# Project_2.net
KiCad netlist of a schematic drawn in EAGLE
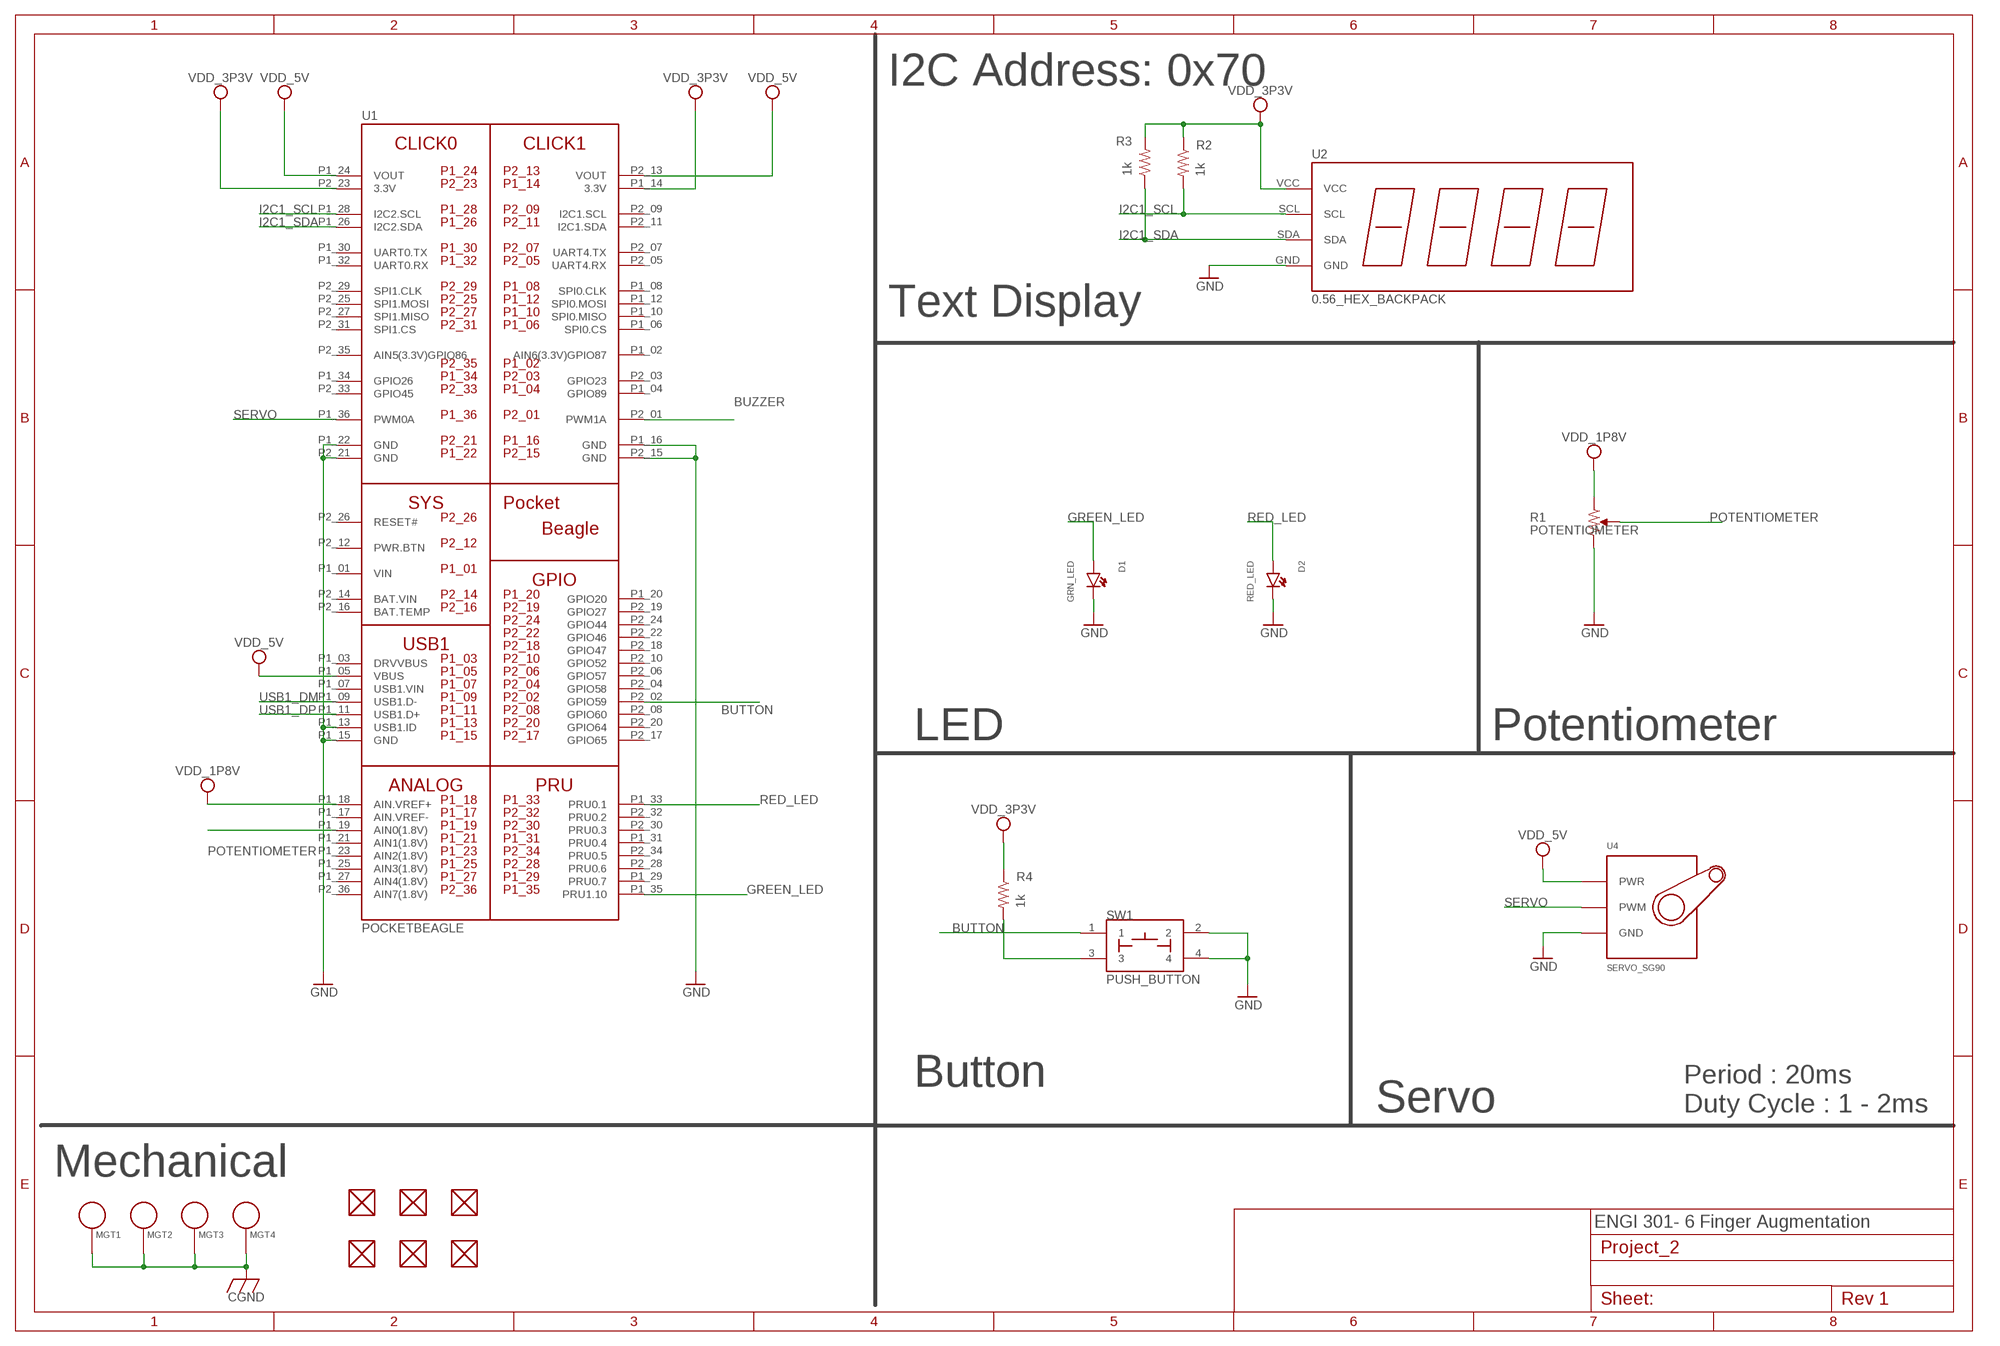
[diagram p0: schematic, sheet 1]

(export (version "E")
  (design (tool "Eeschema 10.0.6"))
  (components
    (comp (ref "D1")
      (value "GRN_LED")
      (footprint "eagle-import:EIA-STD")
      (libsource (lib "eagle-import") (part "LED"))
    )
    (comp (ref "D2")
      (value "RED_LED")
      (footprint "eagle-import:EIA-STD")
      (libsource (lib "eagle-import") (part "LED"))
    )
    (comp (ref "FUD1")
      (value "FIDUCIAL")
      (footprint "eagle-import:FIDUCIAL_40MIL")
      (libsource (lib "eagle-import") (part "FIDUCIAL"))
    )
    (comp (ref "FUD2")
      (value "FIDUCIAL")
      (footprint "eagle-import:FIDUCIAL_40MIL")
      (libsource (lib "eagle-import") (part "FIDUCIAL"))
    )
    (comp (ref "FUD3")
      (value "FIDUCIAL")
      (footprint "eagle-import:FIDUCIAL_40MIL")
      (libsource (lib "eagle-import") (part "FIDUCIAL"))
    )
    (comp (ref "FUD4")
      (value "FIDUCIAL")
      (footprint "eagle-import:FIDUCIAL_40MIL")
      (libsource (lib "eagle-import") (part "FIDUCIAL"))
    )
    (comp (ref "FUD5")
      (value "FIDUCIAL")
      (footprint "eagle-import:FIDUCIAL_40MIL")
      (libsource (lib "eagle-import") (part "FIDUCIAL"))
    )
    (comp (ref "FUD6")
      (value "FIDUCIAL")
      (footprint "eagle-import:FIDUCIAL_40MIL")
      (libsource (lib "eagle-import") (part "FIDUCIAL"))
    )
    (comp (ref "MGT1")
      (value "MOUNTING_HOLE")
      (footprint "eagle-import:MOUNTING_HOLE")
      (libsource (lib "eagle-import") (part "MOUNTING_HOLE"))
    )
    (comp (ref "MGT2")
      (value "MOUNTING_HOLE")
      (footprint "eagle-import:MOUNTING_HOLE")
      (libsource (lib "eagle-import") (part "MOUNTING_HOLE"))
    )
    (comp (ref "MGT3")
      (value "MOUNTING_HOLE")
      (footprint "eagle-import:MOUNTING_HOLE")
      (libsource (lib "eagle-import") (part "MOUNTING_HOLE"))
    )
    (comp (ref "MGT4")
      (value "MOUNTING_HOLE")
      (footprint "eagle-import:MOUNTING_HOLE")
      (libsource (lib "eagle-import") (part "MOUNTING_HOLE"))
    )
    (comp (ref "R1")
      (value "POTENTIOMETER")
      (footprint "eagle-import:POT-PO90S")
      (libsource (lib "eagle-import") (part "POTENTIOMETER"))
    )
    (comp (ref "R2")
      (value "1k")
      (footprint "eagle-import:R0603")
      (libsource (lib "eagle-import") (part "R_R0603"))
    )
    (comp (ref "R3")
      (value "1k")
      (footprint "eagle-import:R0603")
      (libsource (lib "eagle-import") (part "R_R0603"))
    )
    (comp (ref "R4")
      (value "1k")
      (footprint "eagle-import:R0603")
      (libsource (lib "eagle-import") (part "R_R0603"))
    )
    (comp (ref "SW1")
      (value "PUSH_BUTTON")
      (footprint "eagle-import:BUTTON_12.5MM")
      (libsource (lib "eagle-import") (part "PUSH_BUTTON"))
    )
    (comp (ref "U1")
      (value "POCKETBEAGLE")
      (footprint "eagle-import:POCKETBEAGLE")
      (libsource (lib "eagle-import") (part "POCKETBEAGLE"))
    )
    (comp (ref "U2")
      (value "0.56_HEX_BACKPACK")
      (footprint "eagle-import:0.56_HEX_BACKPACK")
      (libsource (lib "eagle-import") (part "0.56_HEX_BACKPACK"))
    )
    (comp (ref "U4")
      (value "SERVO_SG90")
      (footprint "eagle-import:SERVO-X1")
      (libsource (lib "eagle-import") (part "SERVO_SG90"))
    )
  )
  (nets
    (net (code "1") (name "/BAT.VIN") (class "Default")
      (node (ref "U1") (pin "P2_14") (pinfunction "BAT.VIN_P2_14") (pintype "power_in"))
    )
    (net (code "2") (name "/BUTTON") (class "Default")
      (node (ref "R4") (pin "2") (pinfunction "2_2") (pintype "passive"))
      (node (ref "SW1") (pin "1") (pinfunction "1_1") (pintype "bidirectional"))
      (node (ref "SW1") (pin "3") (pinfunction "3_3") (pintype "bidirectional"))
      (node (ref "U1") (pin "P2_02") (pinfunction "GPIO59_P2_02") (pintype "bidirectional"))
    )
    (net (code "3") (name "/BUZZER") (class "Default")
      (node (ref "U1") (pin "P2_01") (pinfunction "PWM1A_P2_01") (pintype "bidirectional"))
    )
    (net (code "4") (name "/GREEN_LED") (class "Default")
      (node (ref "D1") (pin "ANODE") (pinfunction "ANODE_ANODE") (pintype "bidirectional"))
      (node (ref "U1") (pin "P1_35") (pinfunction "PRU1.10_P1_35") (pintype "bidirectional"))
    )
    (net (code "5") (name "/I2C1_SCL") (class "Default")
      (node (ref "R2") (pin "2") (pinfunction "2_2") (pintype "passive"))
      (node (ref "U1") (pin "P1_28") (pinfunction "I2C2.SCL_P1_28") (pintype "bidirectional"))
      (node (ref "U2") (pin "SCL") (pinfunction "SCL_SCL") (pintype "bidirectional"))
    )
    (net (code "6") (name "/I2C1_SDA") (class "Default")
      (node (ref "R3") (pin "1") (pinfunction "1_1") (pintype "passive"))
      (node (ref "U1") (pin "P1_26") (pinfunction "I2C2.SDA_P1_26") (pintype "bidirectional"))
      (node (ref "U2") (pin "SDA") (pinfunction "SDA_SDA") (pintype "bidirectional"))
    )
    (net (code "7") (name "/POTENTIOMETER") (class "Default")
      (node (ref "R1") (pin "S") (pinfunction "S_S") (pintype "bidirectional"))
      (node (ref "U1") (pin "P1_19") (pinfunction "AIN0(1.8V)_P1_19") (pintype "input"))
    )
    (net (code "8") (name "/RED_LED") (class "Default")
      (node (ref "D2") (pin "ANODE") (pinfunction "ANODE_ANODE") (pintype "bidirectional"))
      (node (ref "U1") (pin "P1_33") (pinfunction "PRU0.1_P1_33") (pintype "bidirectional"))
    )
    (net (code "9") (name "/SERVO") (class "Default")
      (node (ref "U1") (pin "P1_36") (pinfunction "PWM0A_P1_36") (pintype "bidirectional"))
      (node (ref "U4") (pin "SIG") (pinfunction "PWM_SIG") (pintype "bidirectional"))
    )
    (net (code "10") (name "/USB1_DM") (class "Default")
      (node (ref "U1") (pin "P1_09") (pinfunction "USB1.D-_P1_09") (pintype "bidirectional"))
    )
    (net (code "11") (name "/USB1_DP") (class "Default")
      (node (ref "U1") (pin "P1_11") (pinfunction "USB1.D+_P1_11") (pintype "bidirectional"))
    )
    (net (code "12") (name "/VIN") (class "Default")
      (node (ref "U1") (pin "P1_01") (pinfunction "VIN_P1_01") (pintype "power_in"))
    )
    (net (code "13") (name "CGND") (class "Default")
      (node (ref "MGT1") (pin "P$1") (pinfunction "P$1_P$1") (pintype "bidirectional"))
      (node (ref "MGT2") (pin "P$1") (pinfunction "P$1_P$1") (pintype "bidirectional"))
      (node (ref "MGT3") (pin "P$1") (pinfunction "P$1_P$1") (pintype "bidirectional"))
      (node (ref "MGT4") (pin "P$1") (pinfunction "P$1_P$1") (pintype "bidirectional"))
    )
    (net (code "14") (name "GND") (class "Default")
      (node (ref "D1") (pin "CATHODE") (pinfunction "CATHODE_CATHODE") (pintype "bidirectional"))
      (node (ref "D2") (pin "CATHODE") (pinfunction "CATHODE_CATHODE") (pintype "bidirectional"))
      (node (ref "R1") (pin "CW") (pinfunction "CW_CW") (pintype "passive"))
      (node (ref "SW1") (pin "2") (pinfunction "2_2") (pintype "bidirectional"))
      (node (ref "SW1") (pin "4") (pinfunction "4_4") (pintype "bidirectional"))
      (node (ref "U1") (pin "P1_13") (pinfunction "USB1.ID_P1_13") (pintype "bidirectional"))
      (node (ref "U1") (pin "P1_15") (pinfunction "GND_P1_15") (pintype "bidirectional"))
      (node (ref "U1") (pin "P1_16") (pinfunction "GND_P1_16") (pintype "power_in"))
      (node (ref "U1") (pin "P1_22") (pinfunction "GND_P1_22") (pintype "power_in"))
      (node (ref "U1") (pin "P2_15") (pinfunction "GND_P2_15") (pintype "power_in"))
      (node (ref "U1") (pin "P2_21") (pinfunction "GND_P2_21") (pintype "power_in"))
      (node (ref "U2") (pin "GND") (pinfunction "GND_GND") (pintype "bidirectional"))
      (node (ref "U4") (pin "GND") (pinfunction "GND_GND") (pintype "bidirectional"))
    )
    (net (code "15") (name "VDD_1P8V") (class "Default")
      (node (ref "R1") (pin "CCW") (pinfunction "CCW_CCW") (pintype "passive"))
      (node (ref "U1") (pin "P1_18") (pinfunction "AIN.VREF+_P1_18") (pintype "input"))
    )
    (net (code "16") (name "VDD_3P3V") (class "Default")
      (node (ref "R2") (pin "1") (pinfunction "1_1") (pintype "passive"))
      (node (ref "R3") (pin "2") (pinfunction "2_2") (pintype "passive"))
      (node (ref "R4") (pin "1") (pinfunction "1_1") (pintype "passive"))
      (node (ref "U1") (pin "P1_14") (pinfunction "3.3V_P1_14") (pintype "power_in"))
      (node (ref "U1") (pin "P2_23") (pinfunction "3.3V_P2_23") (pintype "power_in"))
      (node (ref "U2") (pin "VCC") (pinfunction "VCC_VCC") (pintype "power_in"))
    )
    (net (code "17") (name "VDD_5V") (class "Default")
      (node (ref "U1") (pin "P1_05") (pinfunction "VBUS_P1_05") (pintype "bidirectional"))
      (node (ref "U1") (pin "P1_24") (pinfunction "VOUT_P1_24") (pintype "power_in"))
      (node (ref "U1") (pin "P2_13") (pinfunction "VOUT_P2_13") (pintype "power_in"))
      (node (ref "U4") (pin "PWR") (pinfunction "PWR_PWR") (pintype "bidirectional"))
    )
    (net (code "18") (name "unconnected-(FUD1-PadP$1)") (class "Default")
      (node (ref "FUD1") (pin "P$1") (pinfunction "P$1_P$1") (pintype "no_connect"))
    )
    (net (code "19") (name "unconnected-(FUD2-PadP$1)") (class "Default")
      (node (ref "FUD2") (pin "P$1") (pinfunction "P$1_P$1") (pintype "no_connect"))
    )
    (net (code "20") (name "unconnected-(FUD3-PadP$1)") (class "Default")
      (node (ref "FUD3") (pin "P$1") (pinfunction "P$1_P$1") (pintype "no_connect"))
    )
    (net (code "21") (name "unconnected-(FUD4-PadP$1)") (class "Default")
      (node (ref "FUD4") (pin "P$1") (pinfunction "P$1_P$1") (pintype "no_connect"))
    )
    (net (code "22") (name "unconnected-(FUD5-PadP$1)") (class "Default")
      (node (ref "FUD5") (pin "P$1") (pinfunction "P$1_P$1") (pintype "no_connect"))
    )
    (net (code "23") (name "unconnected-(FUD6-PadP$1)") (class "Default")
      (node (ref "FUD6") (pin "P$1") (pinfunction "P$1_P$1") (pintype "no_connect"))
    )
    (net (code "24") (name "unconnected-(U1-AIN.VREF--PadP1_17)") (class "Default")
      (node (ref "U1") (pin "P1_17") (pinfunction "AIN.VREF-_P1_17") (pintype "input"))
    )
    (net (code "25") (name "unconnected-(U1-AIN1(1.8V)-PadP1_21)") (class "Default")
      (node (ref "U1") (pin "P1_21") (pinfunction "AIN1(1.8V)_P1_21") (pintype "input"))
    )
    (net (code "26") (name "unconnected-(U1-AIN2(1.8V)-PadP1_23)") (class "Default")
      (node (ref "U1") (pin "P1_23") (pinfunction "AIN2(1.8V)_P1_23") (pintype "input"))
    )
    (net (code "27") (name "unconnected-(U1-AIN3(1.8V)-PadP1_25)") (class "Default")
      (node (ref "U1") (pin "P1_25") (pinfunction "AIN3(1.8V)_P1_25") (pintype "input"))
    )
    (net (code "28") (name "unconnected-(U1-AIN4(1.8V)-PadP1_27)") (class "Default")
      (node (ref "U1") (pin "P1_27") (pinfunction "AIN4(1.8V)_P1_27") (pintype "input"))
    )
    (net (code "29") (name "unconnected-(U1-AIN5(3.3V)GPIO86-PadP2_35)") (class "Default")
      (node (ref "U1") (pin "P2_35") (pinfunction "AIN5(3.3V)GPIO86_P2_35") (pintype "bidirectional"))
    )
    (net (code "30") (name "unconnected-(U1-AIN6(3.3V)GPIO87-PadP1_02)") (class "Default")
      (node (ref "U1") (pin "P1_02") (pinfunction "AIN6(3.3V)GPIO87_P1_02") (pintype "bidirectional"))
    )
    (net (code "31") (name "unconnected-(U1-AIN7(1.8V)-PadP2_36)") (class "Default")
      (node (ref "U1") (pin "P2_36") (pinfunction "AIN7(1.8V)_P2_36") (pintype "input"))
    )
    (net (code "32") (name "unconnected-(U1-BAT.TEMP-PadP2_16)") (class "Default")
      (node (ref "U1") (pin "P2_16") (pinfunction "BAT.TEMP_P2_16") (pintype "input"))
    )
    (net (code "33") (name "unconnected-(U1-DRVVBUS-PadP1_03)") (class "Default")
      (node (ref "U1") (pin "P1_03") (pinfunction "DRVVBUS_P1_03") (pintype "bidirectional"))
    )
    (net (code "34") (name "unconnected-(U1-GPIO20-PadP1_20)") (class "Default")
      (node (ref "U1") (pin "P1_20") (pinfunction "GPIO20_P1_20") (pintype "bidirectional"))
    )
    (net (code "35") (name "unconnected-(U1-GPIO23-PadP2_03)") (class "Default")
      (node (ref "U1") (pin "P2_03") (pinfunction "GPIO23_P2_03") (pintype "bidirectional"))
    )
    (net (code "36") (name "unconnected-(U1-GPIO26-PadP1_34)") (class "Default")
      (node (ref "U1") (pin "P1_34") (pinfunction "GPIO26_P1_34") (pintype "bidirectional"))
    )
    (net (code "37") (name "unconnected-(U1-GPIO27-PadP2_19)") (class "Default")
      (node (ref "U1") (pin "P2_19") (pinfunction "GPIO27_P2_19") (pintype "bidirectional"))
    )
    (net (code "38") (name "unconnected-(U1-GPIO44-PadP2_24)") (class "Default")
      (node (ref "U1") (pin "P2_24") (pinfunction "GPIO44_P2_24") (pintype "bidirectional"))
    )
    (net (code "39") (name "unconnected-(U1-GPIO45-PadP2_33)") (class "Default")
      (node (ref "U1") (pin "P2_33") (pinfunction "GPIO45_P2_33") (pintype "bidirectional"))
    )
    (net (code "40") (name "unconnected-(U1-GPIO46-PadP2_22)") (class "Default")
      (node (ref "U1") (pin "P2_22") (pinfunction "GPIO46_P2_22") (pintype "bidirectional"))
    )
    (net (code "41") (name "unconnected-(U1-GPIO47-PadP2_18)") (class "Default")
      (node (ref "U1") (pin "P2_18") (pinfunction "GPIO47_P2_18") (pintype "bidirectional"))
    )
    (net (code "42") (name "unconnected-(U1-GPIO52-PadP2_10)") (class "Default")
      (node (ref "U1") (pin "P2_10") (pinfunction "GPIO52_P2_10") (pintype "bidirectional"))
    )
    (net (code "43") (name "unconnected-(U1-GPIO57-PadP2_06)") (class "Default")
      (node (ref "U1") (pin "P2_06") (pinfunction "GPIO57_P2_06") (pintype "bidirectional"))
    )
    (net (code "44") (name "unconnected-(U1-GPIO58-PadP2_04)") (class "Default")
      (node (ref "U1") (pin "P2_04") (pinfunction "GPIO58_P2_04") (pintype "bidirectional"))
    )
    (net (code "45") (name "unconnected-(U1-GPIO60-PadP2_08)") (class "Default")
      (node (ref "U1") (pin "P2_08") (pinfunction "GPIO60_P2_08") (pintype "bidirectional"))
    )
    (net (code "46") (name "unconnected-(U1-GPIO64-PadP2_20)") (class "Default")
      (node (ref "U1") (pin "P2_20") (pinfunction "GPIO64_P2_20") (pintype "bidirectional"))
    )
    (net (code "47") (name "unconnected-(U1-GPIO65-PadP2_17)") (class "Default")
      (node (ref "U1") (pin "P2_17") (pinfunction "GPIO65_P2_17") (pintype "bidirectional"))
    )
    (net (code "48") (name "unconnected-(U1-GPIO89-PadP1_04)") (class "Default")
      (node (ref "U1") (pin "P1_04") (pinfunction "GPIO89_P1_04") (pintype "bidirectional"))
    )
    (net (code "49") (name "unconnected-(U1-I2C1.SCL-PadP2_09)") (class "Default")
      (node (ref "U1") (pin "P2_09") (pinfunction "I2C1.SCL_P2_09") (pintype "bidirectional"))
    )
    (net (code "50") (name "unconnected-(U1-I2C1.SDA-PadP2_11)") (class "Default")
      (node (ref "U1") (pin "P2_11") (pinfunction "I2C1.SDA_P2_11") (pintype "bidirectional"))
    )
    (net (code "51") (name "unconnected-(U1-PRU0.2-PadP2_32)") (class "Default")
      (node (ref "U1") (pin "P2_32") (pinfunction "PRU0.2_P2_32") (pintype "bidirectional"))
    )
    (net (code "52") (name "unconnected-(U1-PRU0.3-PadP2_30)") (class "Default")
      (node (ref "U1") (pin "P2_30") (pinfunction "PRU0.3_P2_30") (pintype "bidirectional"))
    )
    (net (code "53") (name "unconnected-(U1-PRU0.4-PadP1_31)") (class "Default")
      (node (ref "U1") (pin "P1_31") (pinfunction "PRU0.4_P1_31") (pintype "bidirectional"))
    )
    (net (code "54") (name "unconnected-(U1-PRU0.5-PadP2_34)") (class "Default")
      (node (ref "U1") (pin "P2_34") (pinfunction "PRU0.5_P2_34") (pintype "bidirectional"))
    )
    (net (code "55") (name "unconnected-(U1-PRU0.6-PadP2_28)") (class "Default")
      (node (ref "U1") (pin "P2_28") (pinfunction "PRU0.6_P2_28") (pintype "bidirectional"))
    )
    (net (code "56") (name "unconnected-(U1-PRU0.7-PadP1_29)") (class "Default")
      (node (ref "U1") (pin "P1_29") (pinfunction "PRU0.7_P1_29") (pintype "bidirectional"))
    )
    (net (code "57") (name "unconnected-(U1-PWR.BTN-PadP2_12)") (class "Default")
      (node (ref "U1") (pin "P2_12") (pinfunction "PWR.BTN_P2_12") (pintype "input"))
    )
    (net (code "58") (name "unconnected-(U1-RESET#-PadP2_26)") (class "Default")
      (node (ref "U1") (pin "P2_26") (pinfunction "RESET#_P2_26") (pintype "input"))
    )
    (net (code "59") (name "unconnected-(U1-SPI0.CLK-PadP1_08)") (class "Default")
      (node (ref "U1") (pin "P1_08") (pinfunction "SPI0.CLK_P1_08") (pintype "bidirectional"))
    )
    (net (code "60") (name "unconnected-(U1-SPI0.CS-PadP1_06)") (class "Default")
      (node (ref "U1") (pin "P1_06") (pinfunction "SPI0.CS_P1_06") (pintype "bidirectional"))
    )
    (net (code "61") (name "unconnected-(U1-SPI0.MISO-PadP1_10)") (class "Default")
      (node (ref "U1") (pin "P1_10") (pinfunction "SPI0.MISO_P1_10") (pintype "bidirectional"))
    )
    (net (code "62") (name "unconnected-(U1-SPI0.MOSI-PadP1_12)") (class "Default")
      (node (ref "U1") (pin "P1_12") (pinfunction "SPI0.MOSI_P1_12") (pintype "bidirectional"))
    )
    (net (code "63") (name "unconnected-(U1-SPI1.CLK-PadP2_29)") (class "Default")
      (node (ref "U1") (pin "P2_29") (pinfunction "SPI1.CLK_P2_29") (pintype "bidirectional"))
    )
    (net (code "64") (name "unconnected-(U1-SPI1.CS-PadP2_31)") (class "Default")
      (node (ref "U1") (pin "P2_31") (pinfunction "SPI1.CS_P2_31") (pintype "bidirectional"))
    )
    (net (code "65") (name "unconnected-(U1-SPI1.MISO-PadP2_27)") (class "Default")
      (node (ref "U1") (pin "P2_27") (pinfunction "SPI1.MISO_P2_27") (pintype "bidirectional"))
    )
    (net (code "66") (name "unconnected-(U1-SPI1.MOSI-PadP2_25)") (class "Default")
      (node (ref "U1") (pin "P2_25") (pinfunction "SPI1.MOSI_P2_25") (pintype "bidirectional"))
    )
    (net (code "67") (name "unconnected-(U1-UART0.RX-PadP1_32)") (class "Default")
      (node (ref "U1") (pin "P1_32") (pinfunction "UART0.RX_P1_32") (pintype "bidirectional"))
    )
    (net (code "68") (name "unconnected-(U1-UART0.TX-PadP1_30)") (class "Default")
      (node (ref "U1") (pin "P1_30") (pinfunction "UART0.TX_P1_30") (pintype "bidirectional"))
    )
    (net (code "69") (name "unconnected-(U1-UART4.RX-PadP2_05)") (class "Default")
      (node (ref "U1") (pin "P2_05") (pinfunction "UART4.RX_P2_05") (pintype "bidirectional"))
    )
    (net (code "70") (name "unconnected-(U1-UART4.TX-PadP2_07)") (class "Default")
      (node (ref "U1") (pin "P2_07") (pinfunction "UART4.TX_P2_07") (pintype "bidirectional"))
    )
    (net (code "71") (name "unconnected-(U1-USB1.VIN-PadP1_07)") (class "Default")
      (node (ref "U1") (pin "P1_07") (pinfunction "USB1.VIN_P1_07") (pintype "bidirectional"))
    )
  )
)
